# mMicroSD.net
KiCad netlist of a schematic drawn in EAGLE
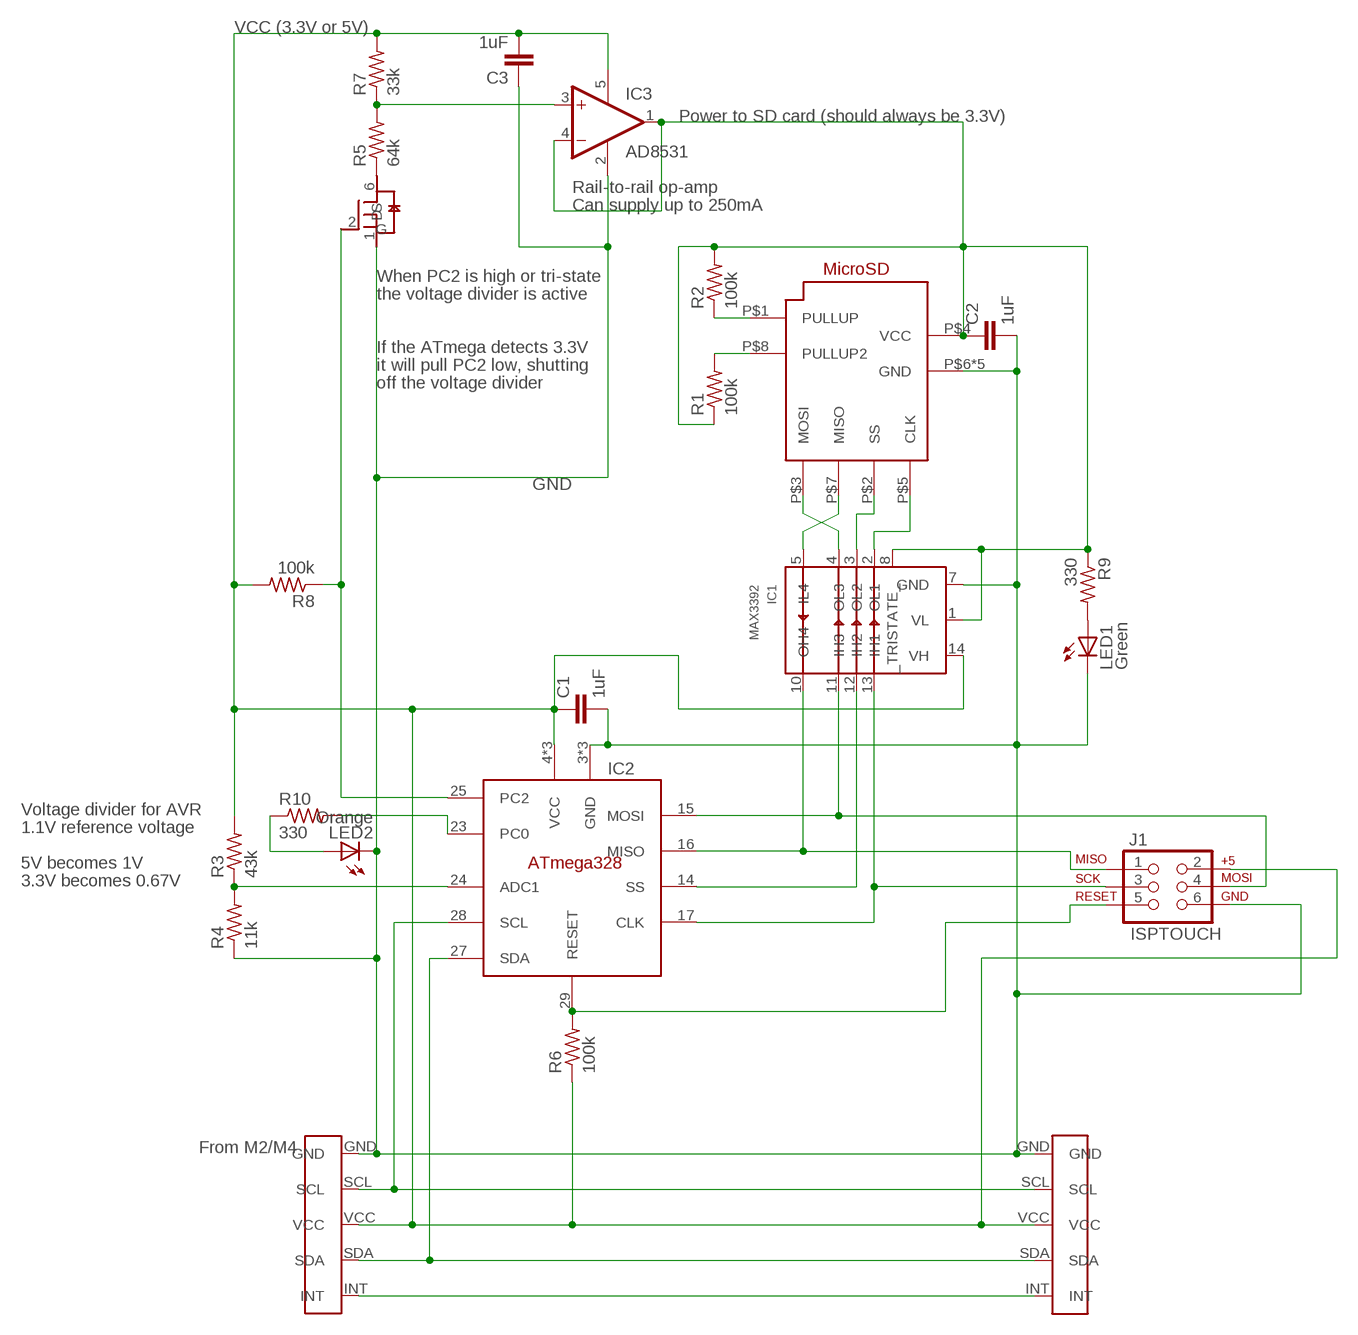
[diagram p0: schematic, sheet 1]

(export (version "E")
  (design (tool "Eeschema 10.0.6"))
  (components
    (comp (ref "C1")
      (value "1uF")
      (footprint "eagle-import:C0603")
      (libsource (lib "eagle-import") (part "C-EUC0603"))
    )
    (comp (ref "C2")
      (value "1uF")
      (footprint "eagle-import:C0603")
      (libsource (lib "eagle-import") (part "C-EUC0603"))
    )
    (comp (ref "C3")
      (value "1uF")
      (footprint "eagle-import:C0603")
      (libsource (lib "eagle-import") (part "C-EUC0603"))
    )
    (comp (ref "IC1")
      (value "MAX3392")
      (footprint "eagle-import:14-TSSOP")
      (libsource (lib "eagle-import") (part "MAX3392"))
    )
    (comp (ref "IC2")
      (value "ATMEGA328")
      (footprint "eagle-import:ATMEGA328")
      (libsource (lib "eagle-import") (part "ATMEGA328"))
    )
    (comp (ref "IC3")
      (value "AD8531")
      (footprint "eagle-import:SOT-23-5")
      (libsource (lib "eagle-import") (part "AD8531"))
    )
    (comp (ref "J1")
      (value "ISPTOUCH")
      (footprint "eagle-import:AVX_9188_6-WAY_SMT")
      (libsource (lib "eagle-import") (part "ISPTOUCH_ADAPTER"))
    )
    (comp (ref "LED1")
      (value "Green")
      (footprint "eagle-import:SML0603")
      (libsource (lib "eagle-import") (part "LEDSML0603"))
    )
    (comp (ref "LED2")
      (value "Orange")
      (footprint "eagle-import:SML0603")
      (libsource (lib "eagle-import") (part "LEDSML0603"))
    )
    (comp (ref "M1")
      (value "NTJD5121N")
      (footprint "eagle-import:SOT-363")
      (libsource (lib "eagle-import") (part "NTJD5121NT1G"))
    )
    (comp (ref "R1")
      (value "100k")
      (footprint "eagle-import:R0603")
      (libsource (lib "eagle-import") (part "R-US_R0603"))
    )
    (comp (ref "R2")
      (value "100k")
      (footprint "eagle-import:R0603")
      (libsource (lib "eagle-import") (part "R-US_R0603"))
    )
    (comp (ref "R3")
      (value "43k")
      (footprint "eagle-import:R0603")
      (libsource (lib "eagle-import") (part "R-US_R0603"))
    )
    (comp (ref "R4")
      (value "11k")
      (footprint "eagle-import:R0603")
      (libsource (lib "eagle-import") (part "R-US_R0603"))
    )
    (comp (ref "R5")
      (value "64k")
      (footprint "eagle-import:R0603")
      (libsource (lib "eagle-import") (part "R-US_R0603"))
    )
    (comp (ref "R6")
      (value "100k")
      (footprint "eagle-import:R0603")
      (libsource (lib "eagle-import") (part "R-US_R0603"))
    )
    (comp (ref "R7")
      (value "33k")
      (footprint "eagle-import:R0603")
      (libsource (lib "eagle-import") (part "R-US_R0603"))
    )
    (comp (ref "R8")
      (value "100k")
      (footprint "eagle-import:R0603")
      (libsource (lib "eagle-import") (part "R-US_R0603"))
    )
    (comp (ref "R9")
      (value "330")
      (footprint "eagle-import:R0603")
      (libsource (lib "eagle-import") (part "R-US_R0603"))
    )
    (comp (ref "R10")
      (value "330")
      (footprint "eagle-import:R0603")
      (libsource (lib "eagle-import") (part "R-US_R0603"))
    )
    (comp (ref "SDCONN")
      (value "101-00660-68-6")
      (footprint "eagle-import:101-00660-68-6")
      (libsource (lib "eagle-import") (part "101-00660-68-6"))
    )
    (comp (ref "U$1")
      (value "MBUS_OUT")
      (footprint "eagle-import:MBUS_OUT")
      (libsource (lib "eagle-import") (part "MBUS_OUT"))
    )
    (comp (ref "U$2")
      (value "MBUS_IN")
      (footprint "eagle-import:MBUS_IN")
      (libsource (lib "eagle-import") (part "MBUS_IN"))
    )
  )
  (nets
    (net (code "1") (name "/GND") (class "Default")
      (node (ref "C1") (pin "2") (pinfunction "2_2") (pintype "passive"))
      (node (ref "C2") (pin "2") (pinfunction "2_2") (pintype "passive"))
      (node (ref "C3") (pin "1") (pinfunction "1_1") (pintype "passive"))
      (node (ref "IC1") (pin "7") (pinfunction "GND_7") (pintype "power_in"))
      (node (ref "IC2") (pin "21") (pinfunction "GND_21") (pintype "bidirectional"))
      (node (ref "IC2") (pin "3") (pinfunction "GND_3") (pintype "bidirectional"))
      (node (ref "IC2") (pin "5") (pinfunction "GND_5") (pintype "bidirectional"))
      (node (ref "IC3") (pin "2") (pinfunction "V-_2") (pintype "power_in"))
      (node (ref "J1") (pin "6") (pinfunction "6_6") (pintype "passive"))
      (node (ref "LED1") (pin "C") (pinfunction "C_C") (pintype "passive"))
      (node (ref "LED2") (pin "C") (pinfunction "C_C") (pintype "passive"))
      (node (ref "M1") (pin "1") (pinfunction "S_1") (pintype "bidirectional"))
      (node (ref "R4") (pin "1") (pinfunction "1_1") (pintype "passive"))
      (node (ref "SDCONN") (pin "P$10") (pinfunction "GND_P$10") (pintype "bidirectional"))
      (node (ref "SDCONN") (pin "P$11") (pinfunction "GND_P$11") (pintype "bidirectional"))
      (node (ref "SDCONN") (pin "P$12") (pinfunction "GND_P$12") (pintype "bidirectional"))
      (node (ref "SDCONN") (pin "P$6") (pinfunction "GND_P$6") (pintype "bidirectional"))
      (node (ref "SDCONN") (pin "P$9") (pinfunction "GND_P$9") (pintype "bidirectional"))
      (node (ref "U$1") (pin "GND") (pinfunction "GND_GND") (pintype "bidirectional"))
      (node (ref "U$2") (pin "GND") (pinfunction "GND_GND") (pintype "bidirectional"))
    )
    (net (code "2") (name "Net-(IC1-IH1)") (class "Default")
      (node (ref "IC1") (pin "13") (pinfunction "IH1_13") (pintype "input"))
      (node (ref "IC2") (pin "17") (pinfunction "CLK_17") (pintype "bidirectional"))
      (node (ref "J1") (pin "3") (pinfunction "3_3") (pintype "passive"))
    )
    (net (code "3") (name "Net-(IC1-IH2)") (class "Default")
      (node (ref "IC1") (pin "12") (pinfunction "IH2_12") (pintype "input"))
      (node (ref "IC2") (pin "14") (pinfunction "SS_14") (pintype "bidirectional"))
    )
    (net (code "4") (name "Net-(IC1-IH3)") (class "Default")
      (node (ref "IC1") (pin "11") (pinfunction "IH3_11") (pintype "input"))
      (node (ref "IC2") (pin "15") (pinfunction "MOSI_15") (pintype "bidirectional"))
      (node (ref "J1") (pin "4") (pinfunction "4_4") (pintype "passive"))
    )
    (net (code "5") (name "Net-(IC1-IL4)") (class "Default")
      (node (ref "IC1") (pin "5") (pinfunction "IL4_5") (pintype "input"))
      (node (ref "SDCONN") (pin "P$7") (pinfunction "MISO_P$7") (pintype "bidirectional"))
    )
    (net (code "6") (name "Net-(IC1-OH4)") (class "Default")
      (node (ref "IC1") (pin "10") (pinfunction "OH4_10") (pintype "output"))
      (node (ref "IC2") (pin "16") (pinfunction "MISO_16") (pintype "bidirectional"))
      (node (ref "J1") (pin "1") (pinfunction "1_1") (pintype "passive"))
    )
    (net (code "7") (name "Net-(IC1-OL1)") (class "Default")
      (node (ref "IC1") (pin "2") (pinfunction "OL1_2") (pintype "output"))
      (node (ref "SDCONN") (pin "P$5") (pinfunction "CLK_P$5") (pintype "bidirectional"))
    )
    (net (code "8") (name "Net-(IC1-OL2)") (class "Default")
      (node (ref "IC1") (pin "3") (pinfunction "OL2_3") (pintype "output"))
      (node (ref "SDCONN") (pin "P$2") (pinfunction "SS_P$2") (pintype "bidirectional"))
    )
    (net (code "9") (name "Net-(IC1-OL3)") (class "Default")
      (node (ref "IC1") (pin "4") (pinfunction "OL3_4") (pintype "output"))
      (node (ref "SDCONN") (pin "P$3") (pinfunction "MOSI_P$3") (pintype "bidirectional"))
    )
    (net (code "10") (name "Net-(IC1-VH)") (class "Default")
      (node (ref "C1") (pin "1") (pinfunction "1_1") (pintype "passive"))
      (node (ref "C3") (pin "2") (pinfunction "2_2") (pintype "passive"))
      (node (ref "IC1") (pin "14") (pinfunction "VH_14") (pintype "power_in"))
      (node (ref "IC2") (pin "18") (pinfunction "VCC_18") (pintype "bidirectional"))
      (node (ref "IC2") (pin "4") (pinfunction "VCC_4") (pintype "bidirectional"))
      (node (ref "IC2") (pin "6") (pinfunction "VCC_6") (pintype "bidirectional"))
      (node (ref "IC3") (pin "5") (pinfunction "V+_5") (pintype "power_in"))
      (node (ref "J1") (pin "2") (pinfunction "2_2") (pintype "passive"))
      (node (ref "R3") (pin "2") (pinfunction "2_2") (pintype "passive"))
      (node (ref "R6") (pin "1") (pinfunction "1_1") (pintype "passive"))
      (node (ref "R7") (pin "2") (pinfunction "2_2") (pintype "passive"))
      (node (ref "R8") (pin "2") (pinfunction "2_2") (pintype "passive"))
      (node (ref "U$1") (pin "VCC") (pinfunction "VCC_VCC") (pintype "bidirectional"))
      (node (ref "U$2") (pin "VCC") (pinfunction "VCC_VCC") (pintype "bidirectional"))
    )
    (net (code "11") (name "Net-(IC1-VL)") (class "Default")
      (node (ref "C2") (pin "1") (pinfunction "1_1") (pintype "passive"))
      (node (ref "IC1") (pin "1") (pinfunction "VL_1") (pintype "power_in"))
      (node (ref "IC1") (pin "8") (pinfunction "_TRISTATE__8") (pintype "input"))
      (node (ref "IC3") (pin "1") (pinfunction "OUT_1") (pintype "output"))
      (node (ref "IC3") (pin "4") (pinfunction "-IN_4") (pintype "input"))
      (node (ref "R1") (pin "1") (pinfunction "1_1") (pintype "passive"))
      (node (ref "R2") (pin "2") (pinfunction "2_2") (pintype "passive"))
      (node (ref "R9") (pin "1") (pinfunction "1_1") (pintype "passive"))
      (node (ref "SDCONN") (pin "P$4") (pinfunction "VCC_P$4") (pintype "bidirectional"))
    )
    (net (code "12") (name "Net-(IC2-ADC1)") (class "Default")
      (node (ref "IC2") (pin "24") (pinfunction "ADC1_24") (pintype "bidirectional"))
      (node (ref "R3") (pin "1") (pinfunction "1_1") (pintype "passive"))
      (node (ref "R4") (pin "2") (pinfunction "2_2") (pintype "passive"))
    )
    (net (code "13") (name "Net-(IC2-PC0)") (class "Default")
      (node (ref "IC2") (pin "23") (pinfunction "PC0_23") (pintype "bidirectional"))
      (node (ref "R10") (pin "2") (pinfunction "2_2") (pintype "passive"))
    )
    (net (code "14") (name "Net-(IC2-PC2)") (class "Default")
      (node (ref "IC2") (pin "25") (pinfunction "PC2_25") (pintype "bidirectional"))
      (node (ref "M1") (pin "2") (pinfunction "G_2") (pintype "bidirectional"))
      (node (ref "R8") (pin "1") (pinfunction "1_1") (pintype "passive"))
    )
    (net (code "15") (name "Net-(IC2-RESET)") (class "Default")
      (node (ref "IC2") (pin "29") (pinfunction "RESET_29") (pintype "bidirectional"))
      (node (ref "J1") (pin "5") (pinfunction "5_5") (pintype "passive"))
      (node (ref "R6") (pin "2") (pinfunction "2_2") (pintype "passive"))
    )
    (net (code "16") (name "Net-(IC2-SCL)") (class "Default")
      (node (ref "IC2") (pin "28") (pinfunction "SCL_28") (pintype "bidirectional"))
      (node (ref "U$1") (pin "SCL") (pinfunction "SCL_SCL") (pintype "bidirectional"))
      (node (ref "U$2") (pin "SCL") (pinfunction "SCL_SCL") (pintype "bidirectional"))
    )
    (net (code "17") (name "Net-(IC2-SDA)") (class "Default")
      (node (ref "IC2") (pin "27") (pinfunction "SDA_27") (pintype "bidirectional"))
      (node (ref "U$1") (pin "SDA") (pinfunction "SDA_SDA") (pintype "bidirectional"))
      (node (ref "U$2") (pin "SDA") (pinfunction "SDA_SDA") (pintype "bidirectional"))
    )
    (net (code "18") (name "Net-(IC3-+IN)") (class "Default")
      (node (ref "IC3") (pin "3") (pinfunction "+IN_3") (pintype "input"))
      (node (ref "R5") (pin "2") (pinfunction "2_2") (pintype "passive"))
      (node (ref "R7") (pin "1") (pinfunction "1_1") (pintype "passive"))
    )
    (net (code "19") (name "Net-(LED1-PadA)") (class "Default")
      (node (ref "LED1") (pin "A") (pinfunction "A_A") (pintype "passive"))
      (node (ref "R9") (pin "2") (pinfunction "2_2") (pintype "passive"))
    )
    (net (code "20") (name "Net-(LED2-PadA)") (class "Default")
      (node (ref "LED2") (pin "A") (pinfunction "A_A") (pintype "passive"))
      (node (ref "R10") (pin "1") (pinfunction "1_1") (pintype "passive"))
    )
    (net (code "21") (name "Net-(M1A-D)") (class "Default")
      (node (ref "M1") (pin "6") (pinfunction "D_6") (pintype "bidirectional"))
      (node (ref "R5") (pin "1") (pinfunction "1_1") (pintype "passive"))
    )
    (net (code "22") (name "Net-(SDCONN-PULLUP)") (class "Default")
      (node (ref "R2") (pin "1") (pinfunction "1_1") (pintype "passive"))
      (node (ref "SDCONN") (pin "P$1") (pinfunction "PULLUP_P$1") (pintype "bidirectional"))
    )
    (net (code "23") (name "Net-(SDCONN-PULLUP2)") (class "Default")
      (node (ref "R1") (pin "2") (pinfunction "2_2") (pintype "passive"))
      (node (ref "SDCONN") (pin "P$8") (pinfunction "PULLUP2_P$8") (pintype "bidirectional"))
    )
    (net (code "24") (name "Net-(U$1-PadINT)") (class "Default")
      (node (ref "U$1") (pin "INT") (pinfunction "INT_INT") (pintype "bidirectional"))
      (node (ref "U$2") (pin "INT") (pinfunction "INT_INT") (pintype "bidirectional"))
    )
  )
)
